# 4809-dip.net
KiCad netlist of a schematic drawn in EAGLE
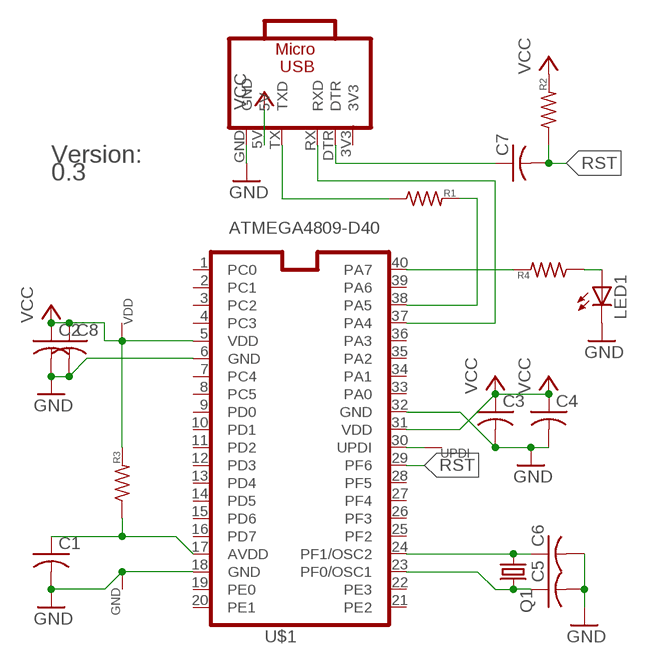
[diagram p0: schematic, sheet 1]

(export (version "E")
  (design (tool "Eeschema 10.0.6"))
  (components
    (comp (ref "C1")
      (value "C-USC0805")
      (footprint "eagle-import:C0805")
      (libsource (lib "eagle-import") (part "C-USC0805"))
    )
    (comp (ref "C2")
      (value "C-USC0805")
      (footprint "eagle-import:C0805")
      (libsource (lib "eagle-import") (part "C-USC0805"))
    )
    (comp (ref "C3")
      (value "C-USC0805")
      (footprint "eagle-import:C0805")
      (libsource (lib "eagle-import") (part "C-USC0805"))
    )
    (comp (ref "C4")
      (value "C-USC0805")
      (footprint "eagle-import:C0805")
      (libsource (lib "eagle-import") (part "C-USC0805"))
    )
    (comp (ref "C5")
      (value "C-USC0805")
      (footprint "eagle-import:C0805")
      (libsource (lib "eagle-import") (part "C-USC0805"))
    )
    (comp (ref "C6")
      (value "C-USC0805")
      (footprint "eagle-import:C0805")
      (libsource (lib "eagle-import") (part "C-USC0805"))
    )
    (comp (ref "C7")
      (value "C-USC0805")
      (footprint "eagle-import:C0805")
      (libsource (lib "eagle-import") (part "C-USC0805"))
    )
    (comp (ref "C8")
      (value "C-USC1206")
      (footprint "eagle-import:C1206")
      (libsource (lib "eagle-import") (part "C-USC1206"))
    )
    (comp (ref "GND")
      (value "WIRE-R10")
      (footprint "eagle-import:VIA10")
      (libsource (lib "eagle-import") (part "WIRE-R10"))
    )
    (comp (ref "LED1")
      (value "LEDCHIP-LED0805")
      (footprint "eagle-import:CHIP-LED0805")
      (libsource (lib "eagle-import") (part "LEDCHIP-LED0805"))
    )
    (comp (ref "MOD1")
      (value "CH340E-MODNOHOLES")
      (footprint "eagle-import:CH340E-MOD-NOHOLES")
      (libsource (lib "eagle-import") (part "CH340E-MODNOHOLES"))
    )
    (comp (ref "Q1")
      (value "CRYSTALMM20SS")
      (footprint "eagle-import:MM20SS")
      (libsource (lib "eagle-import") (part "CRYSTALMM20SS"))
    )
    (comp (ref "R1")
      (value "R-US_R0805")
      (footprint "eagle-import:R0805")
      (libsource (lib "eagle-import") (part "R-US_R0805"))
    )
    (comp (ref "R2")
      (value "R-US_R0805")
      (footprint "eagle-import:R0805")
      (libsource (lib "eagle-import") (part "R-US_R0805"))
    )
    (comp (ref "R3")
      (value "R-US_R0805")
      (footprint "eagle-import:R0805")
      (libsource (lib "eagle-import") (part "R-US_R0805"))
    )
    (comp (ref "R4")
      (value "R-US_R0805")
      (footprint "eagle-import:R0805")
      (libsource (lib "eagle-import") (part "R-US_R0805"))
    )
    (comp (ref "U$1")
      (value "ATMEGA4809-D40")
      (footprint "eagle-import:DIL40SOC")
      (libsource (lib "eagle-import") (part "ATMEGA4809-D40"))
    )
    (comp (ref "UPDI")
      (value "WIRE-R10")
      (footprint "eagle-import:VIA10")
      (libsource (lib "eagle-import") (part "WIRE-R10"))
    )
    (comp (ref "VDD")
      (value "WIRE-R10")
      (footprint "eagle-import:VIA10")
      (libsource (lib "eagle-import") (part "WIRE-R10"))
    )
    (comp (ref "VS1")
      (value "0.3")
      (footprint "eagle-import:VERSIONSTRING")
      (libsource (lib "eagle-import") (part "VERSIONSTRING"))
    )
  )
  (nets
    (net (code "1") (name "/3V3") (class "Default")
      (node (ref "MOD1") (pin "3V3") (pinfunction "3V3_3V3") (pintype "power_in"))
    )
    (net (code "2") (name "GND") (class "Default")
      (node (ref "C1") (pin "2") (pinfunction "2_2") (pintype "passive"))
      (node (ref "C2") (pin "2") (pinfunction "2_2") (pintype "passive"))
      (node (ref "C3") (pin "2") (pinfunction "2_2") (pintype "passive"))
      (node (ref "C4") (pin "2") (pinfunction "2_2") (pintype "passive"))
      (node (ref "C5") (pin "2") (pinfunction "2_2") (pintype "passive"))
      (node (ref "C6") (pin "2") (pinfunction "2_2") (pintype "passive"))
      (node (ref "C8") (pin "2") (pinfunction "2_2") (pintype "passive"))
      (node (ref "GND") (pin "P$1") (pinfunction "P$1_P$1") (pintype "bidirectional"))
      (node (ref "LED1") (pin "C") (pinfunction "C_C") (pintype "passive"))
      (node (ref "MOD1") (pin "GND") (pinfunction "GND_GND") (pintype "power_in"))
      (node (ref "U$1") (pin "18") (pinfunction "GND_18") (pintype "power_in"))
      (node (ref "U$1") (pin "32") (pinfunction "GND_32") (pintype "power_in"))
      (node (ref "U$1") (pin "6") (pinfunction "GND_6") (pintype "power_in"))
    )
    (net (code "3") (name "Net-(C7-Pad1)") (class "Default")
      (node (ref "C7") (pin "1") (pinfunction "1_1") (pintype "passive"))
      (node (ref "MOD1") (pin "DTR") (pinfunction "DTR_DTR") (pintype "output"))
    )
    (net (code "4") (name "Net-(LED1-PadA)") (class "Default")
      (node (ref "LED1") (pin "A") (pinfunction "A_A") (pintype "passive"))
      (node (ref "R4") (pin "1") (pinfunction "1_1") (pintype "passive"))
    )
    (net (code "5") (name "Net-(MOD1-RXD)") (class "Default")
      (node (ref "MOD1") (pin "RX") (pinfunction "RXD_RX") (pintype "input"))
      (node (ref "U$1") (pin "37") (pinfunction "PA4_37") (pintype "bidirectional"))
    )
    (net (code "6") (name "Net-(MOD1-TXD)") (class "Default")
      (node (ref "MOD1") (pin "TX") (pinfunction "TXD_TX") (pintype "output"))
      (node (ref "R1") (pin "1") (pinfunction "1_1") (pintype "passive"))
    )
    (net (code "7") (name "Net-(Q1-2)") (class "Default")
      (node (ref "C5") (pin "1") (pinfunction "1_1") (pintype "passive"))
      (node (ref "Q1") (pin "4") (pinfunction "2_4") (pintype "passive"))
      (node (ref "U$1") (pin "23") (pinfunction "PF0/OSC1_23") (pintype "bidirectional"))
    )
    (net (code "8") (name "Net-(U$1-AVDD)") (class "Default")
      (node (ref "C1") (pin "1") (pinfunction "1_1") (pintype "passive"))
      (node (ref "R3") (pin "1") (pinfunction "1_1") (pintype "passive"))
      (node (ref "U$1") (pin "17") (pinfunction "AVDD_17") (pintype "power_in"))
    )
    (net (code "9") (name "Net-(U$1-PA5)") (class "Default")
      (node (ref "R1") (pin "2") (pinfunction "2_2") (pintype "passive"))
      (node (ref "U$1") (pin "38") (pinfunction "PA5_38") (pintype "bidirectional"))
    )
    (net (code "10") (name "Net-(U$1-PA7)") (class "Default")
      (node (ref "R4") (pin "2") (pinfunction "2_2") (pintype "passive"))
      (node (ref "U$1") (pin "40") (pinfunction "PA7_40") (pintype "bidirectional"))
    )
    (net (code "11") (name "Net-(U$1-PF1{slash}OSC2)") (class "Default")
      (node (ref "C6") (pin "1") (pinfunction "1_1") (pintype "passive"))
      (node (ref "Q1") (pin "1") (pinfunction "1_1") (pintype "passive"))
      (node (ref "U$1") (pin "24") (pinfunction "PF1/OSC2_24") (pintype "bidirectional"))
    )
    (net (code "12") (name "Net-(U$1-UPDI)") (class "Default")
      (node (ref "U$1") (pin "30") (pinfunction "UPDI_30") (pintype "bidirectional"))
      (node (ref "UPDI") (pin "P$1") (pinfunction "P$1_P$1") (pintype "bidirectional"))
    )
    (net (code "13") (name "RST") (class "Default")
      (node (ref "C7") (pin "2") (pinfunction "2_2") (pintype "passive"))
      (node (ref "R2") (pin "1") (pinfunction "1_1") (pintype "passive"))
      (node (ref "U$1") (pin "29") (pinfunction "PF6_29") (pintype "bidirectional"))
    )
    (net (code "14") (name "VCC") (class "Default")
      (node (ref "C2") (pin "1") (pinfunction "1_1") (pintype "passive"))
      (node (ref "C3") (pin "1") (pinfunction "1_1") (pintype "passive"))
      (node (ref "C4") (pin "1") (pinfunction "1_1") (pintype "passive"))
      (node (ref "C8") (pin "1") (pinfunction "1_1") (pintype "passive"))
      (node (ref "MOD1") (pin "5V") (pinfunction "5V_5V") (pintype "power_in"))
      (node (ref "R2") (pin "2") (pinfunction "2_2") (pintype "passive"))
      (node (ref "R3") (pin "2") (pinfunction "2_2") (pintype "passive"))
      (node (ref "U$1") (pin "31") (pinfunction "VDD_31") (pintype "power_in"))
      (node (ref "U$1") (pin "5") (pinfunction "VDD_5") (pintype "power_in"))
      (node (ref "VDD") (pin "P$1") (pinfunction "P$1_P$1") (pintype "bidirectional"))
    )
    (net (code "15") (name "unconnected-(U$1-PA0-Pad33)") (class "Default")
      (node (ref "U$1") (pin "33") (pinfunction "PA0_33") (pintype "bidirectional"))
    )
    (net (code "16") (name "unconnected-(U$1-PA1-Pad34)") (class "Default")
      (node (ref "U$1") (pin "34") (pinfunction "PA1_34") (pintype "bidirectional"))
    )
    (net (code "17") (name "unconnected-(U$1-PA2-Pad35)") (class "Default")
      (node (ref "U$1") (pin "35") (pinfunction "PA2_35") (pintype "bidirectional"))
    )
    (net (code "18") (name "unconnected-(U$1-PA3-Pad36)") (class "Default")
      (node (ref "U$1") (pin "36") (pinfunction "PA3_36") (pintype "bidirectional"))
    )
    (net (code "19") (name "unconnected-(U$1-PA6-Pad39)") (class "Default")
      (node (ref "U$1") (pin "39") (pinfunction "PA6_39") (pintype "bidirectional"))
    )
    (net (code "20") (name "unconnected-(U$1-PC0-Pad1)") (class "Default")
      (node (ref "U$1") (pin "1") (pinfunction "PC0_1") (pintype "bidirectional"))
    )
    (net (code "21") (name "unconnected-(U$1-PC1-Pad2)") (class "Default")
      (node (ref "U$1") (pin "2") (pinfunction "PC1_2") (pintype "bidirectional"))
    )
    (net (code "22") (name "unconnected-(U$1-PC2-Pad3)") (class "Default")
      (node (ref "U$1") (pin "3") (pinfunction "PC2_3") (pintype "bidirectional"))
    )
    (net (code "23") (name "unconnected-(U$1-PC3-Pad4)") (class "Default")
      (node (ref "U$1") (pin "4") (pinfunction "PC3_4") (pintype "bidirectional"))
    )
    (net (code "24") (name "unconnected-(U$1-PC4-Pad7)") (class "Default")
      (node (ref "U$1") (pin "7") (pinfunction "PC4_7") (pintype "bidirectional"))
    )
    (net (code "25") (name "unconnected-(U$1-PC5-Pad8)") (class "Default")
      (node (ref "U$1") (pin "8") (pinfunction "PC5_8") (pintype "bidirectional"))
    )
    (net (code "26") (name "unconnected-(U$1-PD0-Pad9)") (class "Default")
      (node (ref "U$1") (pin "9") (pinfunction "PD0_9") (pintype "bidirectional"))
    )
    (net (code "27") (name "unconnected-(U$1-PD1-Pad10)") (class "Default")
      (node (ref "U$1") (pin "10") (pinfunction "PD1_10") (pintype "bidirectional"))
    )
    (net (code "28") (name "unconnected-(U$1-PD2-Pad11)") (class "Default")
      (node (ref "U$1") (pin "11") (pinfunction "PD2_11") (pintype "bidirectional"))
    )
    (net (code "29") (name "unconnected-(U$1-PD3-Pad12)") (class "Default")
      (node (ref "U$1") (pin "12") (pinfunction "PD3_12") (pintype "bidirectional"))
    )
    (net (code "30") (name "unconnected-(U$1-PD4-Pad13)") (class "Default")
      (node (ref "U$1") (pin "13") (pinfunction "PD4_13") (pintype "bidirectional"))
    )
    (net (code "31") (name "unconnected-(U$1-PD5-Pad14)") (class "Default")
      (node (ref "U$1") (pin "14") (pinfunction "PD5_14") (pintype "bidirectional"))
    )
    (net (code "32") (name "unconnected-(U$1-PD6-Pad15)") (class "Default")
      (node (ref "U$1") (pin "15") (pinfunction "PD6_15") (pintype "bidirectional"))
    )
    (net (code "33") (name "unconnected-(U$1-PD7-Pad16)") (class "Default")
      (node (ref "U$1") (pin "16") (pinfunction "PD7_16") (pintype "bidirectional"))
    )
    (net (code "34") (name "unconnected-(U$1-PE0-Pad19)") (class "Default")
      (node (ref "U$1") (pin "19") (pinfunction "PE0_19") (pintype "bidirectional"))
    )
    (net (code "35") (name "unconnected-(U$1-PE1-Pad20)") (class "Default")
      (node (ref "U$1") (pin "20") (pinfunction "PE1_20") (pintype "bidirectional"))
    )
    (net (code "36") (name "unconnected-(U$1-PE2-Pad21)") (class "Default")
      (node (ref "U$1") (pin "21") (pinfunction "PE2_21") (pintype "bidirectional"))
    )
    (net (code "37") (name "unconnected-(U$1-PE3-Pad22)") (class "Default")
      (node (ref "U$1") (pin "22") (pinfunction "PE3_22") (pintype "bidirectional"))
    )
    (net (code "38") (name "unconnected-(U$1-PF2-Pad25)") (class "Default")
      (node (ref "U$1") (pin "25") (pinfunction "PF2_25") (pintype "bidirectional"))
    )
    (net (code "39") (name "unconnected-(U$1-PF3-Pad26)") (class "Default")
      (node (ref "U$1") (pin "26") (pinfunction "PF3_26") (pintype "bidirectional"))
    )
    (net (code "40") (name "unconnected-(U$1-PF4-Pad27)") (class "Default")
      (node (ref "U$1") (pin "27") (pinfunction "PF4_27") (pintype "bidirectional"))
    )
    (net (code "41") (name "unconnected-(U$1-PF5-Pad28)") (class "Default")
      (node (ref "U$1") (pin "28") (pinfunction "PF5_28") (pintype "bidirectional"))
    )
  )
)
